# SDRAM.net
KiCad netlist of a schematic drawn in Altium Designer
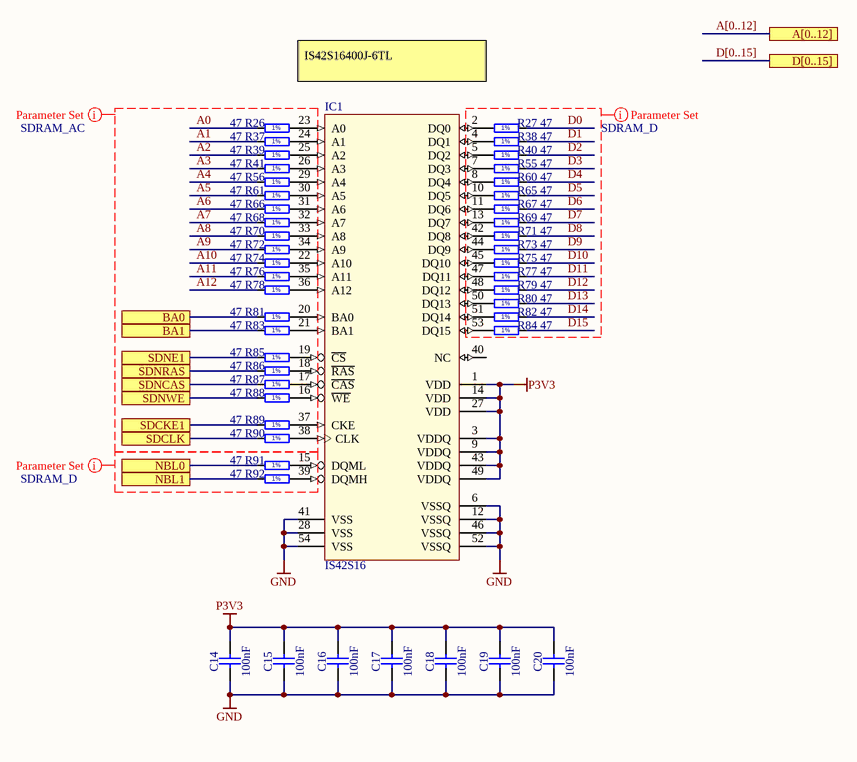
[diagram p0: SDRAM.SchDoc]

(export (version "E")
  (design (tool "Eeschema 10.0.6"))
  (components
    (comp (ref "C14")
      (value "100nF")
      (footprint "CAPC1005X55N")
      (description "Non-polarised capacitor")
      (fields
        (field (name "PART NUMBER") "CC0402_100NF_16V_10%_X5R")
        (field (name "VOLTAGE") "16V")
        (field (name "AUTHOR") "CERN DEM JLC")
      )
      (libsource (lib "Capacitors") (part "Capacitor - non polarized"))
    )
    (comp (ref "C15")
      (value "100nF")
      (footprint "CAPC1005X55N")
      (description "Non-polarised capacitor")
      (fields
        (field (name "PART NUMBER") "CC0402_100NF_16V_10%_X5R")
        (field (name "VOLTAGE") "16V")
        (field (name "AUTHOR") "CERN DEM JLC")
      )
      (libsource (lib "Capacitors") (part "Capacitor - non polarized"))
    )
    (comp (ref "C16")
      (value "100nF")
      (footprint "CAPC1005X55N")
      (description "Non-polarised capacitor")
      (fields
        (field (name "PART NUMBER") "CC0402_100NF_16V_10%_X5R")
        (field (name "VOLTAGE") "16V")
        (field (name "AUTHOR") "CERN DEM JLC")
      )
      (libsource (lib "Capacitors") (part "Capacitor - non polarized"))
    )
    (comp (ref "C17")
      (value "100nF")
      (footprint "CAPC1005X55N")
      (description "Non-polarised capacitor")
      (fields
        (field (name "PART NUMBER") "CC0402_100NF_16V_10%_X5R")
        (field (name "VOLTAGE") "16V")
        (field (name "AUTHOR") "CERN DEM JLC")
      )
      (libsource (lib "Capacitors") (part "Capacitor - non polarized"))
    )
    (comp (ref "C18")
      (value "100nF")
      (footprint "CAPC1005X55N")
      (description "Non-polarised capacitor")
      (fields
        (field (name "PART NUMBER") "CC0402_100NF_16V_10%_X5R")
        (field (name "VOLTAGE") "16V")
        (field (name "AUTHOR") "CERN DEM JLC")
      )
      (libsource (lib "Capacitors") (part "Capacitor - non polarized"))
    )
    (comp (ref "C19")
      (value "100nF")
      (footprint "CAPC1005X55N")
      (description "Non-polarised capacitor")
      (fields
        (field (name "PART NUMBER") "CC0402_100NF_16V_10%_X5R")
        (field (name "VOLTAGE") "16V")
        (field (name "AUTHOR") "CERN DEM JLC")
      )
      (libsource (lib "Capacitors") (part "Capacitor - non polarized"))
    )
    (comp (ref "C20")
      (value "100nF")
      (footprint "CAPC1005X55N")
      (description "Non-polarised capacitor")
      (fields
        (field (name "PART NUMBER") "CC0402_100NF_16V_10%_X5R")
        (field (name "VOLTAGE") "16V")
        (field (name "AUTHOR") "CERN DEM JLC")
      )
      (libsource (lib "Capacitors") (part "Capacitor - non polarized"))
    )
    (comp (ref "IC1")
      (value "IS42S16")
      (footprint "TSOP-54")
      (description "SDRAM 64m 200mhz 54tsop")
      (fields (field (name "MP") "IS42S16400J-5TL-TR") (field (name "MF") "ISSI"))
      (libsource (lib "IS42S16") (part "IS42S16"))
    )
    (comp (ref "R26")
      (value "47")
      (footprint "RESC1005X40N")
      (description "Resistor - 1%")
      (fields
        (field (name "PART NUMBER") "R0402_47R_1%_0.0625W_100PPM")
        (field (name "POWER") "0.0625W")
        (field (name "AUTHOR") "CERN DEM JLC")
      )
      (libsource (lib "Resistors") (part "Resistor - 1%"))
    )
    (comp (ref "R27")
      (value "47")
      (footprint "RESC1005X40N")
      (description "Resistor - 1%")
      (fields
        (field (name "PART NUMBER") "R0402_47R_1%_0.0625W_100PPM")
        (field (name "POWER") "0.0625W")
        (field (name "AUTHOR") "CERN DEM JLC")
      )
      (libsource (lib "Resistors") (part "Resistor - 1%"))
    )
    (comp (ref "R37")
      (value "47")
      (footprint "RESC1005X40N")
      (description "Resistor - 1%")
      (fields
        (field (name "PART NUMBER") "R0402_47R_1%_0.0625W_100PPM")
        (field (name "POWER") "0.0625W")
        (field (name "AUTHOR") "CERN DEM JLC")
      )
      (libsource (lib "Resistors") (part "Resistor - 1%"))
    )
    (comp (ref "R38")
      (value "47")
      (footprint "RESC1005X40N")
      (description "Resistor - 1%")
      (fields
        (field (name "PART NUMBER") "R0402_47R_1%_0.0625W_100PPM")
        (field (name "POWER") "0.0625W")
        (field (name "AUTHOR") "CERN DEM JLC")
      )
      (libsource (lib "Resistors") (part "Resistor - 1%"))
    )
    (comp (ref "R39")
      (value "47")
      (footprint "RESC1005X40N")
      (description "Resistor - 1%")
      (fields
        (field (name "PART NUMBER") "R0402_47R_1%_0.0625W_100PPM")
        (field (name "POWER") "0.0625W")
        (field (name "AUTHOR") "CERN DEM JLC")
      )
      (libsource (lib "Resistors") (part "Resistor - 1%"))
    )
    (comp (ref "R40")
      (value "47")
      (footprint "RESC1005X40N")
      (description "Resistor - 1%")
      (fields
        (field (name "PART NUMBER") "R0402_47R_1%_0.0625W_100PPM")
        (field (name "POWER") "0.0625W")
        (field (name "AUTHOR") "CERN DEM JLC")
      )
      (libsource (lib "Resistors") (part "Resistor - 1%"))
    )
    (comp (ref "R41")
      (value "47")
      (footprint "RESC1005X40N")
      (description "Resistor - 1%")
      (fields
        (field (name "PART NUMBER") "R0402_47R_1%_0.0625W_100PPM")
        (field (name "POWER") "0.0625W")
        (field (name "AUTHOR") "CERN DEM JLC")
      )
      (libsource (lib "Resistors") (part "Resistor - 1%"))
    )
    (comp (ref "R55")
      (value "47")
      (footprint "RESC1005X40N")
      (description "Resistor - 1%")
      (fields
        (field (name "PART NUMBER") "R0402_47R_1%_0.0625W_100PPM")
        (field (name "POWER") "0.0625W")
        (field (name "AUTHOR") "CERN DEM JLC")
      )
      (libsource (lib "Resistors") (part "Resistor - 1%"))
    )
    (comp (ref "R56")
      (value "47")
      (footprint "RESC1005X40N")
      (description "Resistor - 1%")
      (fields
        (field (name "PART NUMBER") "R0402_47R_1%_0.0625W_100PPM")
        (field (name "POWER") "0.0625W")
        (field (name "AUTHOR") "CERN DEM JLC")
      )
      (libsource (lib "Resistors") (part "Resistor - 1%"))
    )
    (comp (ref "R60")
      (value "47")
      (footprint "RESC1005X40N")
      (description "Resistor - 1%")
      (fields
        (field (name "PART NUMBER") "R0402_47R_1%_0.0625W_100PPM")
        (field (name "POWER") "0.0625W")
        (field (name "AUTHOR") "CERN DEM JLC")
      )
      (libsource (lib "Resistors") (part "Resistor - 1%"))
    )
    (comp (ref "R61")
      (value "47")
      (footprint "RESC1005X40N")
      (description "Resistor - 1%")
      (fields
        (field (name "PART NUMBER") "R0402_47R_1%_0.0625W_100PPM")
        (field (name "POWER") "0.0625W")
        (field (name "AUTHOR") "CERN DEM JLC")
      )
      (libsource (lib "Resistors") (part "Resistor - 1%"))
    )
    (comp (ref "R65")
      (value "47")
      (footprint "RESC1005X40N")
      (description "Resistor - 1%")
      (fields
        (field (name "PART NUMBER") "R0402_47R_1%_0.0625W_100PPM")
        (field (name "POWER") "0.0625W")
        (field (name "AUTHOR") "CERN DEM JLC")
      )
      (libsource (lib "Resistors") (part "Resistor - 1%"))
    )
    (comp (ref "R66")
      (value "47")
      (footprint "RESC1005X40N")
      (description "Resistor - 1%")
      (fields
        (field (name "PART NUMBER") "R0402_47R_1%_0.0625W_100PPM")
        (field (name "POWER") "0.0625W")
        (field (name "AUTHOR") "CERN DEM JLC")
      )
      (libsource (lib "Resistors") (part "Resistor - 1%"))
    )
    (comp (ref "R67")
      (value "47")
      (footprint "RESC1005X40N")
      (description "Resistor - 1%")
      (fields
        (field (name "PART NUMBER") "R0402_47R_1%_0.0625W_100PPM")
        (field (name "POWER") "0.0625W")
        (field (name "AUTHOR") "CERN DEM JLC")
      )
      (libsource (lib "Resistors") (part "Resistor - 1%"))
    )
    (comp (ref "R68")
      (value "47")
      (footprint "RESC1005X40N")
      (description "Resistor - 1%")
      (fields
        (field (name "PART NUMBER") "R0402_47R_1%_0.0625W_100PPM")
        (field (name "POWER") "0.0625W")
        (field (name "AUTHOR") "CERN DEM JLC")
      )
      (libsource (lib "Resistors") (part "Resistor - 1%"))
    )
    (comp (ref "R69")
      (value "47")
      (footprint "RESC1005X40N")
      (description "Resistor - 1%")
      (fields
        (field (name "PART NUMBER") "R0402_47R_1%_0.0625W_100PPM")
        (field (name "POWER") "0.0625W")
        (field (name "AUTHOR") "CERN DEM JLC")
      )
      (libsource (lib "Resistors") (part "Resistor - 1%"))
    )
    (comp (ref "R70")
      (value "47")
      (footprint "RESC1005X40N")
      (description "Resistor - 1%")
      (fields
        (field (name "PART NUMBER") "R0402_47R_1%_0.0625W_100PPM")
        (field (name "POWER") "0.0625W")
        (field (name "AUTHOR") "CERN DEM JLC")
      )
      (libsource (lib "Resistors") (part "Resistor - 1%"))
    )
    (comp (ref "R71")
      (value "47")
      (footprint "RESC1005X40N")
      (description "Resistor - 1%")
      (fields
        (field (name "PART NUMBER") "R0402_47R_1%_0.0625W_100PPM")
        (field (name "POWER") "0.0625W")
        (field (name "AUTHOR") "CERN DEM JLC")
      )
      (libsource (lib "Resistors") (part "Resistor - 1%"))
    )
    (comp (ref "R72")
      (value "47")
      (footprint "RESC1005X40N")
      (description "Resistor - 1%")
      (fields
        (field (name "PART NUMBER") "R0402_47R_1%_0.0625W_100PPM")
        (field (name "POWER") "0.0625W")
        (field (name "AUTHOR") "CERN DEM JLC")
      )
      (libsource (lib "Resistors") (part "Resistor - 1%"))
    )
    (comp (ref "R73")
      (value "47")
      (footprint "RESC1005X40N")
      (description "Resistor - 1%")
      (fields
        (field (name "PART NUMBER") "R0402_47R_1%_0.0625W_100PPM")
        (field (name "POWER") "0.0625W")
        (field (name "AUTHOR") "CERN DEM JLC")
      )
      (libsource (lib "Resistors") (part "Resistor - 1%"))
    )
    (comp (ref "R74")
      (value "47")
      (footprint "RESC1005X40N")
      (description "Resistor - 1%")
      (fields
        (field (name "PART NUMBER") "R0402_47R_1%_0.0625W_100PPM")
        (field (name "POWER") "0.0625W")
        (field (name "AUTHOR") "CERN DEM JLC")
      )
      (libsource (lib "Resistors") (part "Resistor - 1%"))
    )
    (comp (ref "R75")
      (value "47")
      (footprint "RESC1005X40N")
      (description "Resistor - 1%")
      (fields
        (field (name "PART NUMBER") "R0402_47R_1%_0.0625W_100PPM")
        (field (name "POWER") "0.0625W")
        (field (name "AUTHOR") "CERN DEM JLC")
      )
      (libsource (lib "Resistors") (part "Resistor - 1%"))
    )
    (comp (ref "R76")
      (value "47")
      (footprint "RESC1005X40N")
      (description "Resistor - 1%")
      (fields
        (field (name "PART NUMBER") "R0402_47R_1%_0.0625W_100PPM")
        (field (name "POWER") "0.0625W")
        (field (name "AUTHOR") "CERN DEM JLC")
      )
      (libsource (lib "Resistors") (part "Resistor - 1%"))
    )
    (comp (ref "R77")
      (value "47")
      (footprint "RESC1005X40N")
      (description "Resistor - 1%")
      (fields
        (field (name "PART NUMBER") "R0402_47R_1%_0.0625W_100PPM")
        (field (name "POWER") "0.0625W")
        (field (name "AUTHOR") "CERN DEM JLC")
      )
      (libsource (lib "Resistors") (part "Resistor - 1%"))
    )
    (comp (ref "R78")
      (value "47")
      (footprint "RESC1005X40N")
      (description "Resistor - 1%")
      (fields
        (field (name "PART NUMBER") "R0402_47R_1%_0.0625W_100PPM")
        (field (name "POWER") "0.0625W")
        (field (name "AUTHOR") "CERN DEM JLC")
      )
      (libsource (lib "Resistors") (part "Resistor - 1%"))
    )
    (comp (ref "R79")
      (value "47")
      (footprint "RESC1005X40N")
      (description "Resistor - 1%")
      (fields
        (field (name "PART NUMBER") "R0402_47R_1%_0.0625W_100PPM")
        (field (name "POWER") "0.0625W")
        (field (name "AUTHOR") "CERN DEM JLC")
      )
      (libsource (lib "Resistors") (part "Resistor - 1%"))
    )
    (comp (ref "R80")
      (value "47")
      (footprint "RESC1005X40N")
      (description "Resistor - 1%")
      (fields
        (field (name "PART NUMBER") "R0402_47R_1%_0.0625W_100PPM")
        (field (name "POWER") "0.0625W")
        (field (name "AUTHOR") "CERN DEM JLC")
      )
      (libsource (lib "Resistors") (part "Resistor - 1%"))
    )
    (comp (ref "R81")
      (value "47")
      (footprint "RESC1005X40N")
      (description "Resistor - 1%")
      (fields
        (field (name "PART NUMBER") "R0402_47R_1%_0.0625W_100PPM")
        (field (name "POWER") "0.0625W")
        (field (name "AUTHOR") "CERN DEM JLC")
      )
      (libsource (lib "Resistors") (part "Resistor - 1%"))
    )
    (comp (ref "R82")
      (value "47")
      (footprint "RESC1005X40N")
      (description "Resistor - 1%")
      (fields
        (field (name "PART NUMBER") "R0402_47R_1%_0.0625W_100PPM")
        (field (name "POWER") "0.0625W")
        (field (name "AUTHOR") "CERN DEM JLC")
      )
      (libsource (lib "Resistors") (part "Resistor - 1%"))
    )
    (comp (ref "R83")
      (value "47")
      (footprint "RESC1005X40N")
      (description "Resistor - 1%")
      (fields
        (field (name "PART NUMBER") "R0402_47R_1%_0.0625W_100PPM")
        (field (name "POWER") "0.0625W")
        (field (name "AUTHOR") "CERN DEM JLC")
      )
      (libsource (lib "Resistors") (part "Resistor - 1%"))
    )
    (comp (ref "R84")
      (value "47")
      (footprint "RESC1005X40N")
      (description "Resistor - 1%")
      (fields
        (field (name "PART NUMBER") "R0402_47R_1%_0.0625W_100PPM")
        (field (name "POWER") "0.0625W")
        (field (name "AUTHOR") "CERN DEM JLC")
      )
      (libsource (lib "Resistors") (part "Resistor - 1%"))
    )
    (comp (ref "R85")
      (value "47")
      (footprint "RESC1005X40N")
      (description "Resistor - 1%")
      (fields
        (field (name "PART NUMBER") "R0402_47R_1%_0.0625W_100PPM")
        (field (name "POWER") "0.0625W")
        (field (name "AUTHOR") "CERN DEM JLC")
      )
      (libsource (lib "Resistors") (part "Resistor - 1%"))
    )
    (comp (ref "R86")
      (value "47")
      (footprint "RESC1005X40N")
      (description "Resistor - 1%")
      (fields
        (field (name "PART NUMBER") "R0402_47R_1%_0.0625W_100PPM")
        (field (name "POWER") "0.0625W")
        (field (name "AUTHOR") "CERN DEM JLC")
      )
      (libsource (lib "Resistors") (part "Resistor - 1%"))
    )
    (comp (ref "R87")
      (value "47")
      (footprint "RESC1005X40N")
      (description "Resistor - 1%")
      (fields
        (field (name "PART NUMBER") "R0402_47R_1%_0.0625W_100PPM")
        (field (name "POWER") "0.0625W")
        (field (name "AUTHOR") "CERN DEM JLC")
      )
      (libsource (lib "Resistors") (part "Resistor - 1%"))
    )
    (comp (ref "R88")
      (value "47")
      (footprint "RESC1005X40N")
      (description "Resistor - 1%")
      (fields
        (field (name "PART NUMBER") "R0402_47R_1%_0.0625W_100PPM")
        (field (name "POWER") "0.0625W")
        (field (name "AUTHOR") "CERN DEM JLC")
      )
      (libsource (lib "Resistors") (part "Resistor - 1%"))
    )
    (comp (ref "R89")
      (value "47")
      (footprint "RESC1005X40N")
      (description "Resistor - 1%")
      (fields
        (field (name "PART NUMBER") "R0402_47R_1%_0.0625W_100PPM")
        (field (name "POWER") "0.0625W")
        (field (name "AUTHOR") "CERN DEM JLC")
      )
      (libsource (lib "Resistors") (part "Resistor - 1%"))
    )
    (comp (ref "R90")
      (value "47")
      (footprint "RESC1005X40N")
      (description "Resistor - 1%")
      (fields
        (field (name "PART NUMBER") "R0402_47R_1%_0.0625W_100PPM")
        (field (name "POWER") "0.0625W")
        (field (name "AUTHOR") "CERN DEM JLC")
      )
      (libsource (lib "Resistors") (part "Resistor - 1%"))
    )
    (comp (ref "R91")
      (value "47")
      (footprint "RESC1005X40N")
      (description "Resistor - 1%")
      (fields
        (field (name "PART NUMBER") "R0402_47R_1%_0.0625W_100PPM")
        (field (name "POWER") "0.0625W")
        (field (name "AUTHOR") "CERN DEM JLC")
      )
      (libsource (lib "Resistors") (part "Resistor - 1%"))
    )
    (comp (ref "R92")
      (value "47")
      (footprint "RESC1005X40N")
      (description "Resistor - 1%")
      (fields
        (field (name "PART NUMBER") "R0402_47R_1%_0.0625W_100PPM")
        (field (name "POWER") "0.0625W")
        (field (name "AUTHOR") "CERN DEM JLC")
      )
      (libsource (lib "Resistors") (part "Resistor - 1%"))
    )
  )
  (nets
    (net (code "1") (name "/A0") (class "Default")
      (node (ref "R26") (pin "2") (pinfunction "2_2") (pintype "passive"))
    )
    (net (code "2") (name "/A1") (class "Default")
      (node (ref "R37") (pin "2") (pinfunction "2_2") (pintype "passive"))
    )
    (net (code "3") (name "/A2") (class "Default")
      (node (ref "R39") (pin "2") (pinfunction "2_2") (pintype "passive"))
    )
    (net (code "4") (name "/A3") (class "Default")
      (node (ref "R41") (pin "2") (pinfunction "2_2") (pintype "passive"))
    )
    (net (code "5") (name "/A4") (class "Default")
      (node (ref "R56") (pin "2") (pinfunction "2_2") (pintype "passive"))
    )
    (net (code "6") (name "/A5") (class "Default")
      (node (ref "R61") (pin "2") (pinfunction "2_2") (pintype "passive"))
    )
    (net (code "7") (name "/A6") (class "Default")
      (node (ref "R66") (pin "2") (pinfunction "2_2") (pintype "passive"))
    )
    (net (code "8") (name "/A7") (class "Default")
      (node (ref "R68") (pin "2") (pinfunction "2_2") (pintype "passive"))
    )
    (net (code "9") (name "/A8") (class "Default")
      (node (ref "R70") (pin "2") (pinfunction "2_2") (pintype "passive"))
    )
    (net (code "10") (name "/A9") (class "Default")
      (node (ref "R72") (pin "2") (pinfunction "2_2") (pintype "passive"))
    )
    (net (code "11") (name "/A10") (class "Default")
      (node (ref "R74") (pin "2") (pinfunction "2_2") (pintype "passive"))
    )
    (net (code "12") (name "/A11") (class "Default")
      (node (ref "R76") (pin "2") (pinfunction "2_2") (pintype "passive"))
    )
    (net (code "13") (name "/A12") (class "Default")
      (node (ref "R78") (pin "2") (pinfunction "2_2") (pintype "passive"))
    )
    (net (code "15") (name "/BA0") (class "Default")
      (node (ref "R81") (pin "2") (pinfunction "2_2") (pintype "passive"))
    )
    (net (code "16") (name "/BA1") (class "Default")
      (node (ref "R83") (pin "2") (pinfunction "2_2") (pintype "passive"))
    )
    (net (code "17") (name "/D0") (class "Default")
      (node (ref "R27") (pin "2") (pinfunction "2_2") (pintype "passive"))
    )
    (net (code "18") (name "/D1") (class "Default")
      (node (ref "R38") (pin "2") (pinfunction "2_2") (pintype "passive"))
    )
    (net (code "19") (name "/D2") (class "Default")
      (node (ref "R40") (pin "2") (pinfunction "2_2") (pintype "passive"))
    )
    (net (code "20") (name "/D3") (class "Default")
      (node (ref "R55") (pin "2") (pinfunction "2_2") (pintype "passive"))
    )
    (net (code "21") (name "/D4") (class "Default")
      (node (ref "R60") (pin "2") (pinfunction "2_2") (pintype "passive"))
    )
    (net (code "22") (name "/D5") (class "Default")
      (node (ref "R65") (pin "2") (pinfunction "2_2") (pintype "passive"))
    )
    (net (code "23") (name "/D6") (class "Default")
      (node (ref "R67") (pin "2") (pinfunction "2_2") (pintype "passive"))
    )
    (net (code "24") (name "/D7") (class "Default")
      (node (ref "R69") (pin "2") (pinfunction "2_2") (pintype "passive"))
    )
    (net (code "25") (name "/D8") (class "Default")
      (node (ref "R71") (pin "2") (pinfunction "2_2") (pintype "passive"))
    )
    (net (code "26") (name "/D9") (class "Default")
      (node (ref "R73") (pin "2") (pinfunction "2_2") (pintype "passive"))
    )
    (net (code "27") (name "/D10") (class "Default")
      (node (ref "R75") (pin "2") (pinfunction "2_2") (pintype "passive"))
    )
    (net (code "28") (name "/D11") (class "Default")
      (node (ref "R77") (pin "2") (pinfunction "2_2") (pintype "passive"))
    )
    (net (code "29") (name "/D12") (class "Default")
      (node (ref "R79") (pin "2") (pinfunction "2_2") (pintype "passive"))
    )
    (net (code "30") (name "/D13") (class "Default")
      (node (ref "R80") (pin "2") (pinfunction "2_2") (pintype "passive"))
    )
    (net (code "31") (name "/D14") (class "Default")
      (node (ref "R82") (pin "2") (pinfunction "2_2") (pintype "passive"))
    )
    (net (code "32") (name "/D15") (class "Default")
      (node (ref "R84") (pin "2") (pinfunction "2_2") (pintype "passive"))
    )
    (net (code "34") (name "/NBL0") (class "Default")
      (node (ref "R91") (pin "2") (pinfunction "2_2") (pintype "passive"))
    )
    (net (code "35") (name "/NBL1") (class "Default")
      (node (ref "R92") (pin "2") (pinfunction "2_2") (pintype "passive"))
    )
    (net (code "36") (name "/SDCKE1") (class "Default")
      (node (ref "R89") (pin "2") (pinfunction "2_2") (pintype "passive"))
    )
    (net (code "37") (name "/SDCLK") (class "Default")
      (node (ref "R90") (pin "2") (pinfunction "2_2") (pintype "passive"))
    )
    (net (code "38") (name "/SDNCAS") (class "Default")
      (node (ref "R87") (pin "2") (pinfunction "2_2") (pintype "passive"))
    )
    (net (code "39") (name "/SDNE1") (class "Default")
      (node (ref "R85") (pin "2") (pinfunction "2_2") (pintype "passive"))
    )
    (net (code "40") (name "/SDNRAS") (class "Default")
      (node (ref "R86") (pin "2") (pinfunction "2_2") (pintype "passive"))
    )
    (net (code "41") (name "/SDNWE") (class "Default")
      (node (ref "R88") (pin "2") (pinfunction "2_2") (pintype "passive"))
    )
    (net (code "42") (name "GND") (class "Default")
      (node (ref "C14") (pin "1") (pinfunction "1_1") (pintype "passive"))
      (node (ref "C15") (pin "1") (pinfunction "1_1") (pintype "passive"))
      (node (ref "C16") (pin "1") (pinfunction "1_1") (pintype "passive"))
      (node (ref "C17") (pin "1") (pinfunction "1_1") (pintype "passive"))
      (node (ref "C18") (pin "1") (pinfunction "1_1") (pintype "passive"))
      (node (ref "C19") (pin "1") (pinfunction "1_1") (pintype "passive"))
      (node (ref "C20") (pin "1") (pinfunction "1_1") (pintype "passive"))
      (node (ref "IC1") (pin "12") (pinfunction "VSSQ_12") (pintype "power_in"))
      (node (ref "IC1") (pin "28") (pinfunction "VSS_28") (pintype "power_in"))
      (node (ref "IC1") (pin "41") (pinfunction "VSS_41") (pintype "power_in"))
      (node (ref "IC1") (pin "46") (pinfunction "VSSQ_46") (pintype "power_in"))
      (node (ref "IC1") (pin "52") (pinfunction "VSSQ_52") (pintype "power_in"))
      (node (ref "IC1") (pin "54") (pinfunction "VSS_54") (pintype "power_in"))
      (node (ref "IC1") (pin "6") (pinfunction "VSSQ_6") (pintype "power_in"))
    )
    (net (code "43") (name "Net-(IC1-A0)") (class "Default")
      (node (ref "IC1") (pin "23") (pinfunction "A0_23") (pintype "input"))
      (node (ref "R26") (pin "1") (pinfunction "1_1") (pintype "passive"))
    )
    (net (code "44") (name "Net-(IC1-A1)") (class "Default")
      (node (ref "IC1") (pin "24") (pinfunction "A1_24") (pintype "input"))
      (node (ref "R37") (pin "1") (pinfunction "1_1") (pintype "passive"))
    )
    (net (code "45") (name "Net-(IC1-A2)") (class "Default")
      (node (ref "IC1") (pin "25") (pinfunction "A2_25") (pintype "input"))
      (node (ref "R39") (pin "1") (pinfunction "1_1") (pintype "passive"))
    )
    (net (code "46") (name "Net-(IC1-A3)") (class "Default")
      (node (ref "IC1") (pin "26") (pinfunction "A3_26") (pintype "input"))
      (node (ref "R41") (pin "1") (pinfunction "1_1") (pintype "passive"))
    )
    (net (code "47") (name "Net-(IC1-A4)") (class "Default")
      (node (ref "IC1") (pin "29") (pinfunction "A4_29") (pintype "input"))
      (node (ref "R56") (pin "1") (pinfunction "1_1") (pintype "passive"))
    )
    (net (code "48") (name "Net-(IC1-A5)") (class "Default")
      (node (ref "IC1") (pin "30") (pinfunction "A5_30") (pintype "input"))
      (node (ref "R61") (pin "1") (pinfunction "1_1") (pintype "passive"))
    )
    (net (code "49") (name "Net-(IC1-A6)") (class "Default")
      (node (ref "IC1") (pin "31") (pinfunction "A6_31") (pintype "input"))
      (node (ref "R66") (pin "1") (pinfunction "1_1") (pintype "passive"))
    )
    (net (code "50") (name "Net-(IC1-A7)") (class "Default")
      (node (ref "IC1") (pin "32") (pinfunction "A7_32") (pintype "input"))
      (node (ref "R68") (pin "1") (pinfunction "1_1") (pintype "passive"))
    )
    (net (code "51") (name "Net-(IC1-A8)") (class "Default")
      (node (ref "IC1") (pin "33") (pinfunction "A8_33") (pintype "input"))
      (node (ref "R70") (pin "1") (pinfunction "1_1") (pintype "passive"))
    )
    (net (code "52") (name "Net-(IC1-A9)") (class "Default")
      (node (ref "IC1") (pin "34") (pinfunction "A9_34") (pintype "input"))
      (node (ref "R72") (pin "1") (pinfunction "1_1") (pintype "passive"))
    )
    (net (code "53") (name "Net-(IC1-A10)") (class "Default")
      (node (ref "IC1") (pin "22") (pinfunction "A10_22") (pintype "input"))
      (node (ref "R74") (pin "1") (pinfunction "1_1") (pintype "passive"))
    )
    (net (code "54") (name "Net-(IC1-A11)") (class "Default")
      (node (ref "IC1") (pin "35") (pinfunction "A11_35") (pintype "input"))
      (node (ref "R76") (pin "1") (pinfunction "1_1") (pintype "passive"))
    )
    (net (code "55") (name "Net-(IC1-A12)") (class "Default")
      (node (ref "IC1") (pin "36") (pinfunction "A12_36") (pintype "input"))
      (node (ref "R78") (pin "1") (pinfunction "1_1") (pintype "passive"))
    )
    (net (code "56") (name "Net-(IC1-BA0)") (class "Default")
      (node (ref "IC1") (pin "20") (pinfunction "BA0_20") (pintype "input"))
      (node (ref "R81") (pin "1") (pinfunction "1_1") (pintype "passive"))
    )
    (net (code "57") (name "Net-(IC1-BA1)") (class "Default")
      (node (ref "IC1") (pin "21") (pinfunction "BA1_21") (pintype "input"))
      (node (ref "R83") (pin "1") (pinfunction "1_1") (pintype "passive"))
    )
    (net (code "58") (name "Net-(IC1-CKE)") (class "Default")
      (node (ref "IC1") (pin "37") (pinfunction "CKE_37") (pintype "input"))
      (node (ref "R89") (pin "1") (pinfunction "1_1") (pintype "passive"))
    )
    (net (code "59") (name "Net-(IC1-CLK)") (class "Default")
      (node (ref "IC1") (pin "38") (pinfunction "CLK_38") (pintype "input"))
      (node (ref "R90") (pin "1") (pinfunction "1_1") (pintype "passive"))
    )
    (net (code "60") (name "Net-(IC1-DQ0)") (class "Default")
      (node (ref "IC1") (pin "2") (pinfunction "DQ0_2") (pintype "bidirectional"))
      (node (ref "R27") (pin "1") (pinfunction "1_1") (pintype "passive"))
    )
    (net (code "61") (name "Net-(IC1-DQ1)") (class "Default")
      (node (ref "IC1") (pin "4") (pinfunction "DQ1_4") (pintype "bidirectional"))
      (node (ref "R38") (pin "1") (pinfunction "1_1") (pintype "passive"))
    )
    (net (code "62") (name "Net-(IC1-DQ2)") (class "Default")
      (node (ref "IC1") (pin "5") (pinfunction "DQ2_5") (pintype "bidirectional"))
      (node (ref "R40") (pin "1") (pinfunction "1_1") (pintype "passive"))
    )
    (net (code "63") (name "Net-(IC1-DQ3)") (class "Default")
      (node (ref "IC1") (pin "7") (pinfunction "DQ3_7") (pintype "bidirectional"))
      (node (ref "R55") (pin "1") (pinfunction "1_1") (pintype "passive"))
    )
    (net (code "64") (name "Net-(IC1-DQ4)") (class "Default")
      (node (ref "IC1") (pin "8") (pinfunction "DQ4_8") (pintype "bidirectional"))
      (node (ref "R60") (pin "1") (pinfunction "1_1") (pintype "passive"))
    )
    (net (code "65") (name "Net-(IC1-DQ5)") (class "Default")
      (node (ref "IC1") (pin "10") (pinfunction "DQ5_10") (pintype "bidirectional"))
      (node (ref "R65") (pin "1") (pinfunction "1_1") (pintype "passive"))
    )
    (net (code "66") (name "Net-(IC1-DQ6)") (class "Default")
      (node (ref "IC1") (pin "11") (pinfunction "DQ6_11") (pintype "bidirectional"))
      (node (ref "R67") (pin "1") (pinfunction "1_1") (pintype "passive"))
    )
    (net (code "67") (name "Net-(IC1-DQ7)") (class "Default")
      (node (ref "IC1") (pin "13") (pinfunction "DQ7_13") (pintype "bidirectional"))
      (node (ref "R69") (pin "1") (pinfunction "1_1") (pintype "passive"))
    )
    (net (code "68") (name "Net-(IC1-DQ8)") (class "Default")
      (node (ref "IC1") (pin "42") (pinfunction "DQ8_42") (pintype "bidirectional"))
      (node (ref "R71") (pin "1") (pinfunction "1_1") (pintype "passive"))
    )
    (net (code "69") (name "Net-(IC1-DQ9)") (class "Default")
      (node (ref "IC1") (pin "44") (pinfunction "DQ9_44") (pintype "bidirectional"))
      (node (ref "R73") (pin "1") (pinfunction "1_1") (pintype "passive"))
    )
    (net (code "70") (name "Net-(IC1-DQ10)") (class "Default")
      (node (ref "IC1") (pin "45") (pinfunction "DQ10_45") (pintype "bidirectional"))
      (node (ref "R75") (pin "1") (pinfunction "1_1") (pintype "passive"))
    )
    (net (code "71") (name "Net-(IC1-DQ11)") (class "Default")
      (node (ref "IC1") (pin "47") (pinfunction "DQ11_47") (pintype "bidirectional"))
      (node (ref "R77") (pin "1") (pinfunction "1_1") (pintype "passive"))
    )
    (net (code "72") (name "Net-(IC1-DQ12)") (class "Default")
      (node (ref "IC1") (pin "48") (pinfunction "DQ12_48") (pintype "bidirectional"))
      (node (ref "R79") (pin "1") (pinfunction "1_1") (pintype "passive"))
    )
    (net (code "73") (name "Net-(IC1-DQ13)") (class "Default")
      (node (ref "IC1") (pin "50") (pinfunction "DQ13_50") (pintype "bidirectional"))
      (node (ref "R80") (pin "1") (pinfunction "1_1") (pintype "passive"))
    )
    (net (code "74") (name "Net-(IC1-DQ14)") (class "Default")
      (node (ref "IC1") (pin "51") (pinfunction "DQ14_51") (pintype "bidirectional"))
      (node (ref "R82") (pin "1") (pinfunction "1_1") (pintype "passive"))
    )
    (net (code "75") (name "Net-(IC1-DQ15)") (class "Default")
      (node (ref "IC1") (pin "53") (pinfunction "DQ15_53") (pintype "bidirectional"))
      (node (ref "R84") (pin "1") (pinfunction "1_1") (pintype "passive"))
    )
    (net (code "76") (name "Net-(IC1-DQMH)") (class "Default")
      (node (ref "IC1") (pin "39") (pinfunction "DQMH_39") (pintype "input"))
      (node (ref "R92") (pin "1") (pinfunction "1_1") (pintype "passive"))
    )
    (net (code "77") (name "Net-(IC1-DQML)") (class "Default")
      (node (ref "IC1") (pin "15") (pinfunction "DQML_15") (pintype "input"))
      (node (ref "R91") (pin "1") (pinfunction "1_1") (pintype "passive"))
    )
    (net (code "78") (name "Net-(IC1-~{CAS})") (class "Default")
      (node (ref "IC1") (pin "17") (pinfunction "~{CAS}_17") (pintype "input"))
      (node (ref "R87") (pin "1") (pinfunction "1_1") (pintype "passive"))
    )
    (net (code "79") (name "Net-(IC1-~{CS})") (class "Default")
      (node (ref "IC1") (pin "19") (pinfunction "~{CS}_19") (pintype "input"))
      (node (ref "R85") (pin "1") (pinfunction "1_1") (pintype "passive"))
    )
    (net (code "80") (name "Net-(IC1-~{RAS})") (class "Default")
      (node (ref "IC1") (pin "18") (pinfunction "~{RAS}_18") (pintype "input"))
      (node (ref "R86") (pin "1") (pinfunction "1_1") (pintype "passive"))
    )
    (net (code "81") (name "Net-(IC1-~{WE})") (class "Default")
      (node (ref "IC1") (pin "16") (pinfunction "~{WE}_16") (pintype "input"))
      (node (ref "R88") (pin "1") (pinfunction "1_1") (pintype "passive"))
    )
    (net (code "82") (name "P3V3") (class "Default")
      (node (ref "C14") (pin "2") (pinfunction "2_2") (pintype "passive"))
      (node (ref "C15") (pin "2") (pinfunction "2_2") (pintype "passive"))
      (node (ref "C16") (pin "2") (pinfunction "2_2") (pintype "passive"))
      (node (ref "C17") (pin "2") (pinfunction "2_2") (pintype "passive"))
      (node (ref "C18") (pin "2") (pinfunction "2_2") (pintype "passive"))
      (node (ref "C19") (pin "2") (pinfunction "2_2") (pintype "passive"))
      (node (ref "C20") (pin "2") (pinfunction "2_2") (pintype "passive"))
      (node (ref "IC1") (pin "1") (pinfunction "VDD_1") (pintype "power_in"))
      (node (ref "IC1") (pin "14") (pinfunction "VDD_14") (pintype "power_in"))
      (node (ref "IC1") (pin "27") (pinfunction "VDD_27") (pintype "power_in"))
      (node (ref "IC1") (pin "3") (pinfunction "VDDQ_3") (pintype "power_in"))
      (node (ref "IC1") (pin "43") (pinfunction "VDDQ_43") (pintype "power_in"))
      (node (ref "IC1") (pin "49") (pinfunction "VDDQ_49") (pintype "power_in"))
      (node (ref "IC1") (pin "9") (pinfunction "VDDQ_9") (pintype "power_in"))
    )
    (net (code "83") (name "unconnected-(IC1-NC-Pad40)") (class "Default")
      (node (ref "IC1") (pin "40") (pinfunction "NC_40") (pintype "bidirectional"))
    )
  )
)
